# dvb_s2.net
KiCad netlist of a schematic drawn in Altium Designer
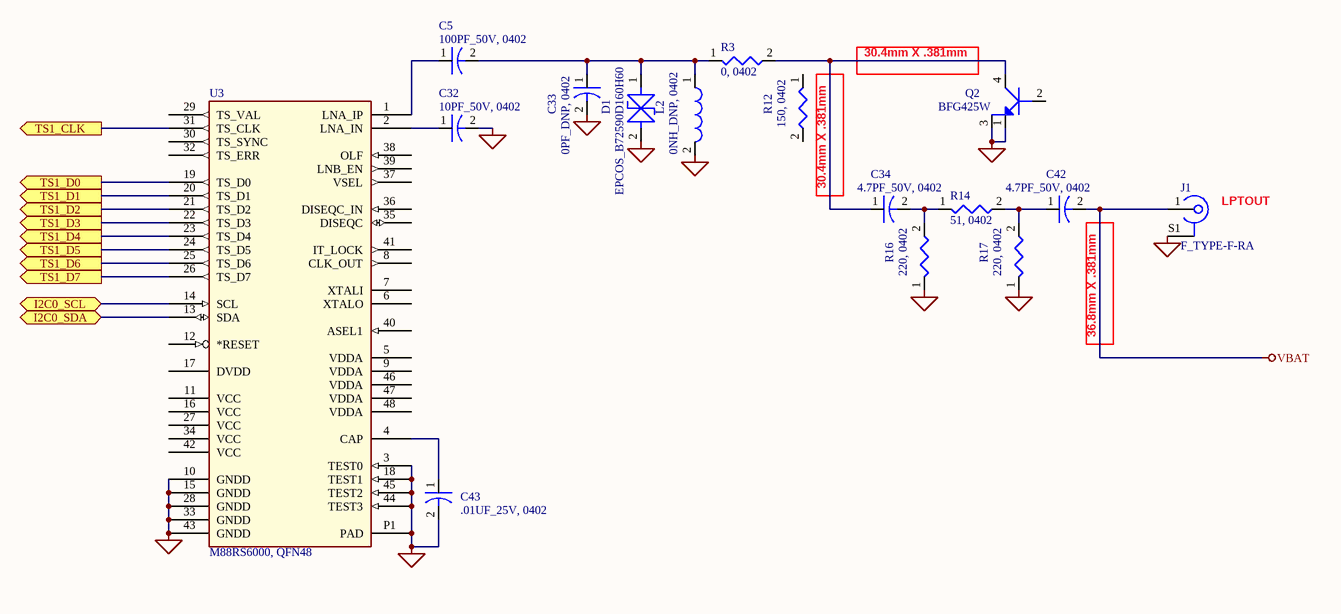
[diagram p0: dvb_s2.SchDoc]

(export (version "E")
  (design (tool "Eeschema 10.0.6"))
  (components
    (comp (ref "C5")
      (value "100PF_50V, 0402")
      (footprint "0402C")
      (description "CAP - 0402 PKG")
      (libsource (lib "COGENT_Library") (part "100PF_50V, 0402"))
    )
    (comp (ref "C32")
      (value "10PF_50V, 0402")
      (footprint "0402C")
      (description "CAP - 0402 PKG")
      (libsource (lib "COGENT_Library") (part "10PF_50V, 0402"))
    )
    (comp (ref "C33")
      (value "0PF_DNP, 0402")
      (footprint "0402C")
      (description "CAP - 0402 PKG")
      (libsource (lib "COGENT_Library") (part "0PF_DNP, 0402"))
    )
    (comp (ref "C34")
      (value "4.7PF_50V, 0402")
      (footprint "0402C")
      (description "CAP - 0402 PKG")
      (libsource (lib "COGENT_Library") (part "4.7PF_50V, 0402"))
    )
    (comp (ref "C42")
      (value "4.7PF_50V, 0402")
      (footprint "0402C")
      (description "CAP - 0402 PKG")
      (libsource (lib "COGENT_Library") (part "4.7PF_50V, 0402"))
    )
    (comp (ref "C43")
      (value ".01UF_25V, 0402")
      (footprint "0402C")
      (description "CAP - 0402 PKG")
      (libsource (lib "COGENT_Library") (part ".01UF_25V, 0402"))
    )
    (comp (ref "D1")
      (value "EPCOS_B72590D160H60")
      (footprint "0402L")
      (description "DIODE - VARISTOR, 16VDC 2PF 0402")
      (libsource (lib "COGENT_Library") (part "EPCOS_B72590D160H60"))
    )
    (comp (ref "J1")
      (value "F_TYPE-F-RA")
      (footprint "F_TYPE-F-RA")
      (description "RF - CONN, F TYPE FEMALE, RIGHT ANGLE")
      (libsource (lib "COGENT_Library") (part "F_TYPE-F-RA"))
    )
    (comp (ref "L2")
      (value "0NH_DNP, 0402")
      (footprint "0402L")
      (description "FERRITE BEAD - 120 OHM, 500MA, 0402 PKG")
      (libsource (lib "COGENT_Library") (part "0NH_DNP, 0402"))
    )
    (comp (ref "Q2")
      (value "BFG425W")
      (footprint "SOT-343R/SC-70-4")
      (description "NPN -  10V, 30ma, GAIN = 80, 25Ghz")
      (libsource (lib "COGENT_Library") (part "BFG425W"))
    )
    (comp (ref "R3")
      (value "0, 0402")
      (footprint "0402R")
      (description "RES - 0402 PKG")
      (libsource (lib "COGENT_Library") (part "0, 0402"))
    )
    (comp (ref "R12")
      (value "150, 0402")
      (footprint "0402R")
      (description "RES - 0402 PKG")
      (libsource (lib "COGENT_Library") (part "150, 0402"))
    )
    (comp (ref "R14")
      (value "51, 0402")
      (footprint "0402R")
      (description "RES - 0402 PKG")
      (libsource (lib "COGENT_Library") (part "51, 0402"))
    )
    (comp (ref "R16")
      (value "220, 0402")
      (footprint "0402R")
      (description "RES - 0402 PKG")
      (libsource (lib "COGENT_Library") (part "220, 0402"))
    )
    (comp (ref "R17")
      (value "220, 0402")
      (footprint "0402R")
      (description "RES - 0402 PKG")
      (libsource (lib "COGENT_Library") (part "220, 0402"))
    )
    (comp (ref "U3")
      (value "M88RS6000, QFN48")
      (footprint "qfn48")
      (description "ANALOG - DB-S2 TUNER AND DEMODULATOR")
      (libsource (lib "COGENT_Library") (part "M88RS6000, QFN48"))
    )
  )
  (nets
    (net (code "1") (name "/I2C0_SCL") (class "Default")
      (node (ref "U3") (pin "14") (pinfunction "SCL_14") (pintype "input"))
    )
    (net (code "2") (name "/I2C0_SDA") (class "Default")
      (node (ref "U3") (pin "13") (pinfunction "SDA_13") (pintype "bidirectional"))
    )
    (net (code "3") (name "/TS1_CLK") (class "Default")
      (node (ref "U3") (pin "31") (pinfunction "TS_CLK_31") (pintype "output"))
    )
    (net (code "4") (name "/TS1_D0") (class "Default")
      (node (ref "U3") (pin "19") (pinfunction "TS_D0_19") (pintype "output"))
    )
    (net (code "5") (name "/TS1_D1") (class "Default")
      (node (ref "U3") (pin "20") (pinfunction "TS_D1_20") (pintype "output"))
    )
    (net (code "6") (name "/TS1_D2") (class "Default")
      (node (ref "U3") (pin "21") (pinfunction "TS_D2_21") (pintype "output"))
    )
    (net (code "7") (name "/TS1_D3") (class "Default")
      (node (ref "U3") (pin "22") (pinfunction "TS_D3_22") (pintype "output"))
    )
    (net (code "8") (name "/TS1_D4") (class "Default")
      (node (ref "U3") (pin "23") (pinfunction "TS_D4_23") (pintype "output"))
    )
    (net (code "9") (name "/TS1_D5") (class "Default")
      (node (ref "U3") (pin "24") (pinfunction "TS_D5_24") (pintype "output"))
    )
    (net (code "10") (name "/TS1_D6") (class "Default")
      (node (ref "U3") (pin "25") (pinfunction "TS_D6_25") (pintype "output"))
    )
    (net (code "11") (name "/TS1_D7") (class "Default")
      (node (ref "U3") (pin "26") (pinfunction "TS_D7_26") (pintype "output"))
    )
    (net (code "12") (name "GND") (class "Default")
      (node (ref "C32") (pin "2") (pinfunction "2_2") (pintype "passive"))
      (node (ref "C33") (pin "2") (pinfunction "2_2") (pintype "passive"))
      (node (ref "C43") (pin "2") (pinfunction "2_2") (pintype "passive"))
      (node (ref "D1") (pin "2") (pinfunction "CATHODE_2") (pintype "passive"))
      (node (ref "J1") (pin "S1") (pinfunction "S1_S1") (pintype "passive"))
      (node (ref "L2") (pin "2") (pinfunction "2_2") (pintype "passive"))
      (node (ref "Q2") (pin "1") (pinfunction "EMITTER_1") (pintype "passive"))
      (node (ref "Q2") (pin "3") (pinfunction "EMITTER_3") (pintype "passive"))
      (node (ref "R16") (pin "1") (pinfunction "1_1") (pintype "passive"))
      (node (ref "R17") (pin "1") (pinfunction "1_1") (pintype "passive"))
      (node (ref "U3") (pin "10") (pinfunction "GNDD_10") (pintype "passive"))
      (node (ref "U3") (pin "15") (pinfunction "GNDD_15") (pintype "passive"))
      (node (ref "U3") (pin "18") (pinfunction "TEST1_18") (pintype "input"))
      (node (ref "U3") (pin "28") (pinfunction "GNDD_28") (pintype "passive"))
      (node (ref "U3") (pin "3") (pinfunction "TEST0_3") (pintype "input"))
      (node (ref "U3") (pin "33") (pinfunction "GNDD_33") (pintype "passive"))
      (node (ref "U3") (pin "43") (pinfunction "GNDD_43") (pintype "passive"))
      (node (ref "U3") (pin "44") (pinfunction "TEST3_44") (pintype "input"))
      (node (ref "U3") (pin "45") (pinfunction "TEST2_45") (pintype "input"))
      (node (ref "U3") (pin "P1") (pinfunction "PAD_P1") (pintype "passive"))
    )
    (net (code "13") (name "Net-(C34-Pad2)") (class "Default")
      (node (ref "C34") (pin "2") (pinfunction "2_2") (pintype "passive"))
      (node (ref "R14") (pin "1") (pinfunction "1_1") (pintype "passive"))
      (node (ref "R16") (pin "2") (pinfunction "2_2") (pintype "passive"))
    )
    (net (code "14") (name "Net-(C42-Pad1)") (class "Default")
      (node (ref "C42") (pin "1") (pinfunction "1_1") (pintype "passive"))
      (node (ref "R14") (pin "2") (pinfunction "2_2") (pintype "passive"))
      (node (ref "R17") (pin "2") (pinfunction "2_2") (pintype "passive"))
    )
    (net (code "15") (name "Net-(D1-ANODE)") (class "Default")
      (node (ref "C33") (pin "1") (pinfunction "1_1") (pintype "passive"))
      (node (ref "C5") (pin "2") (pinfunction "2_2") (pintype "passive"))
      (node (ref "D1") (pin "1") (pinfunction "ANODE_1") (pintype "passive"))
      (node (ref "L2") (pin "1") (pinfunction "1_1") (pintype "passive"))
      (node (ref "R3") (pin "1") (pinfunction "1_1") (pintype "passive"))
    )
    (net (code "16") (name "Net-(Q2-COLLECTOR)") (class "Default")
      (node (ref "C34") (pin "1") (pinfunction "1_1") (pintype "passive"))
      (node (ref "Q2") (pin "4") (pinfunction "COLLECTOR_4") (pintype "passive"))
      (node (ref "R3") (pin "2") (pinfunction "2_2") (pintype "passive"))
    )
    (net (code "17") (name "Net-(U3-CAP)") (class "Default")
      (node (ref "C43") (pin "1") (pinfunction "1_1") (pintype "passive"))
      (node (ref "U3") (pin "4") (pinfunction "CAP_4") (pintype "passive"))
    )
    (net (code "18") (name "Net-(U3-LNA_IN)") (class "Default")
      (node (ref "C32") (pin "1") (pinfunction "1_1") (pintype "passive"))
      (node (ref "U3") (pin "2") (pinfunction "LNA_IN_2") (pintype "passive"))
    )
    (net (code "19") (name "Net-(U3-LNA_IP)") (class "Default")
      (node (ref "C5") (pin "1") (pinfunction "1_1") (pintype "passive"))
      (node (ref "U3") (pin "1") (pinfunction "LNA_IP_1") (pintype "passive"))
    )
    (net (code "20") (name "VBAT") (class "Default")
      (node (ref "C42") (pin "2") (pinfunction "2_2") (pintype "passive"))
      (node (ref "J1") (pin "1") (pinfunction "1_1") (pintype "passive"))
    )
    (net (code "21") (name "unconnected-(Q2-BASE-Pad2)") (class "Default")
      (node (ref "Q2") (pin "2") (pinfunction "BASE_2") (pintype "passive"))
    )
    (net (code "22") (name "unconnected-(R12-Pad1)") (class "Default")
      (node (ref "R12") (pin "1") (pinfunction "1_1") (pintype "passive"))
    )
    (net (code "23") (name "unconnected-(R12-Pad2)") (class "Default")
      (node (ref "R12") (pin "2") (pinfunction "2_2") (pintype "passive"))
    )
    (net (code "24") (name "unconnected-(U3-*RESET-Pad12)") (class "Default")
      (node (ref "U3") (pin "12") (pinfunction "*RESET_12") (pintype "input"))
    )
    (net (code "25") (name "unconnected-(U3-ASEL1-Pad40)") (class "Default")
      (node (ref "U3") (pin "40") (pinfunction "ASEL1_40") (pintype "input"))
    )
    (net (code "26") (name "unconnected-(U3-CLK_OUT-Pad8)") (class "Default")
      (node (ref "U3") (pin "8") (pinfunction "CLK_OUT_8") (pintype "output"))
    )
    (net (code "27") (name "unconnected-(U3-DISEQC-Pad35)") (class "Default")
      (node (ref "U3") (pin "35") (pinfunction "DISEQC_35") (pintype "bidirectional"))
    )
    (net (code "28") (name "unconnected-(U3-DISEQC_IN-Pad36)") (class "Default")
      (node (ref "U3") (pin "36") (pinfunction "DISEQC_IN_36") (pintype "input"))
    )
    (net (code "29") (name "unconnected-(U3-DVDD-Pad17)") (class "Default")
      (node (ref "U3") (pin "17") (pinfunction "DVDD_17") (pintype "passive"))
    )
    (net (code "30") (name "unconnected-(U3-IT_LOCK-Pad41)") (class "Default")
      (node (ref "U3") (pin "41") (pinfunction "IT_LOCK_41") (pintype "output"))
    )
    (net (code "31") (name "unconnected-(U3-LNB_EN-Pad39)") (class "Default")
      (node (ref "U3") (pin "39") (pinfunction "LNB_EN_39") (pintype "output"))
    )
    (net (code "32") (name "unconnected-(U3-OLF-Pad38)") (class "Default")
      (node (ref "U3") (pin "38") (pinfunction "OLF_38") (pintype "input"))
    )
    (net (code "33") (name "unconnected-(U3-TS_ERR-Pad32)") (class "Default")
      (node (ref "U3") (pin "32") (pinfunction "TS_ERR_32") (pintype "output"))
    )
    (net (code "34") (name "unconnected-(U3-TS_SYNC-Pad30)") (class "Default")
      (node (ref "U3") (pin "30") (pinfunction "TS_SYNC_30") (pintype "output"))
    )
    (net (code "35") (name "unconnected-(U3-TS_VAL-Pad29)") (class "Default")
      (node (ref "U3") (pin "29") (pinfunction "TS_VAL_29") (pintype "output"))
    )
    (net (code "36") (name "unconnected-(U3-VCC-Pad11)") (class "Default")
      (node (ref "U3") (pin "11") (pinfunction "VCC_11") (pintype "passive"))
    )
    (net (code "37") (name "unconnected-(U3-VCC-Pad16)") (class "Default")
      (node (ref "U3") (pin "16") (pinfunction "VCC_16") (pintype "passive"))
    )
    (net (code "38") (name "unconnected-(U3-VCC-Pad27)") (class "Default")
      (node (ref "U3") (pin "27") (pinfunction "VCC_27") (pintype "passive"))
    )
    (net (code "39") (name "unconnected-(U3-VCC-Pad34)") (class "Default")
      (node (ref "U3") (pin "34") (pinfunction "VCC_34") (pintype "passive"))
    )
    (net (code "40") (name "unconnected-(U3-VCC-Pad42)") (class "Default")
      (node (ref "U3") (pin "42") (pinfunction "VCC_42") (pintype "passive"))
    )
    (net (code "41") (name "unconnected-(U3-VDDA-Pad5)") (class "Default")
      (node (ref "U3") (pin "5") (pinfunction "VDDA_5") (pintype "passive"))
    )
    (net (code "42") (name "unconnected-(U3-VDDA-Pad9)") (class "Default")
      (node (ref "U3") (pin "9") (pinfunction "VDDA_9") (pintype "passive"))
    )
    (net (code "43") (name "unconnected-(U3-VDDA-Pad46)") (class "Default")
      (node (ref "U3") (pin "46") (pinfunction "VDDA_46") (pintype "passive"))
    )
    (net (code "44") (name "unconnected-(U3-VDDA-Pad47)") (class "Default")
      (node (ref "U3") (pin "47") (pinfunction "VDDA_47") (pintype "passive"))
    )
    (net (code "45") (name "unconnected-(U3-VDDA-Pad48)") (class "Default")
      (node (ref "U3") (pin "48") (pinfunction "VDDA_48") (pintype "passive"))
    )
    (net (code "46") (name "unconnected-(U3-VSEL-Pad37)") (class "Default")
      (node (ref "U3") (pin "37") (pinfunction "VSEL_37") (pintype "output"))
    )
    (net (code "47") (name "unconnected-(U3-XTALI-Pad7)") (class "Default")
      (node (ref "U3") (pin "7") (pinfunction "XTALI_7") (pintype "passive"))
    )
    (net (code "48") (name "unconnected-(U3-XTALO-Pad6)") (class "Default")
      (node (ref "U3") (pin "6") (pinfunction "XTALO_6") (pintype "passive"))
    )
  )
)
